# UWB-Breakout.net
KiCad netlist of a schematic drawn in EAGLE
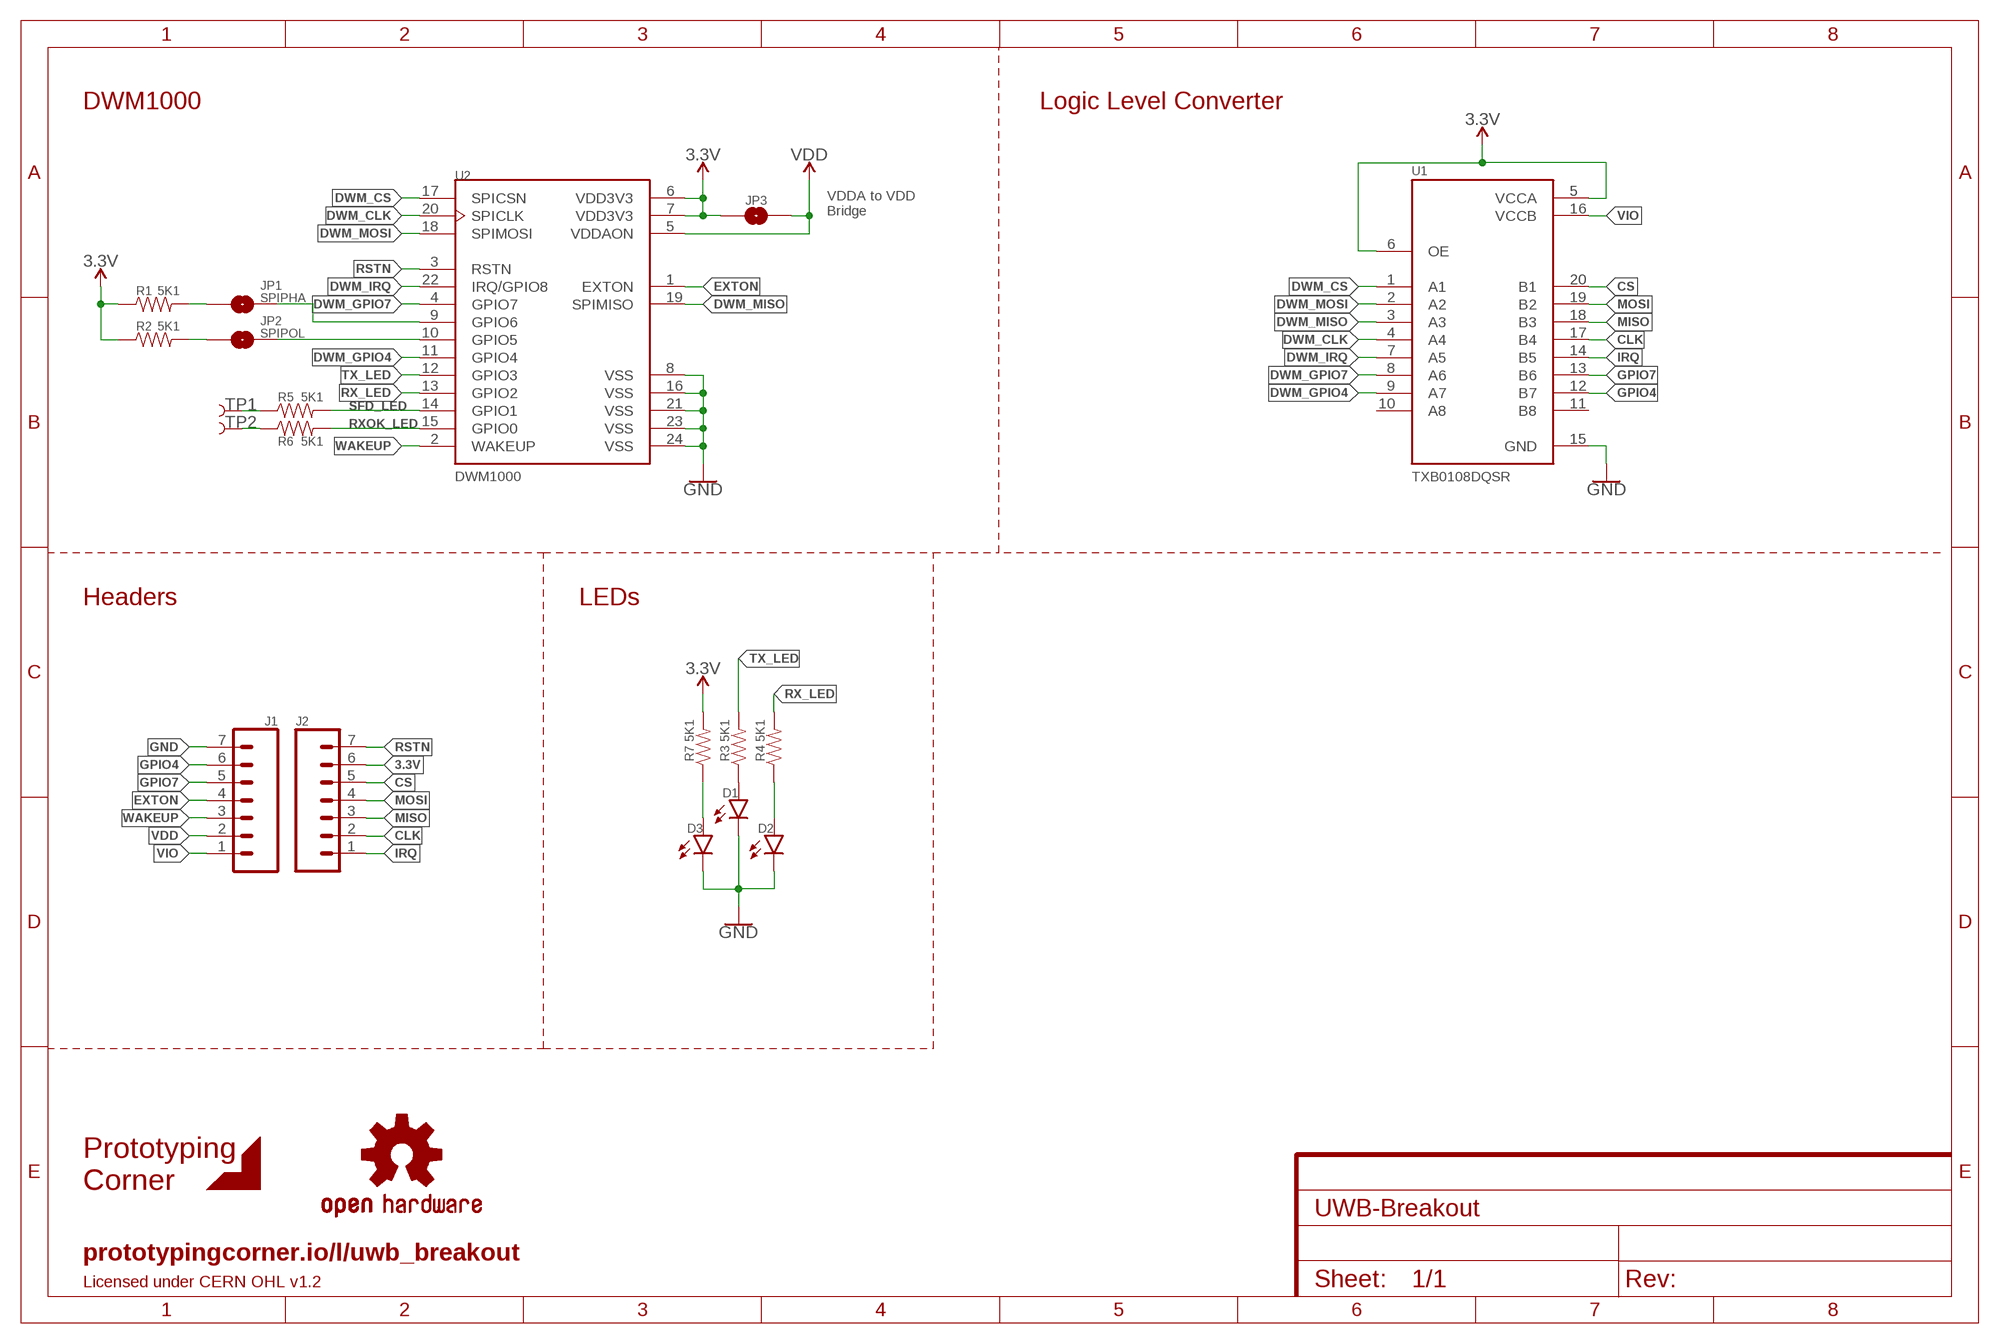
[diagram p0: schematic, sheet 1]

(export (version "E")
  (design (tool "Eeschema 10.0.6"))
  (components
    (comp (ref "D1")
      (value "Yellow")
      (footprint "eagle-import:LED-0603")
      (libsource (lib "eagle-import") (part "LED-YELLOW0603"))
    )
    (comp (ref "D2")
      (value "GREEN")
      (footprint "eagle-import:LED-0603")
      (libsource (lib "eagle-import") (part "LED-GREEN0603"))
    )
    (comp (ref "D3")
      (value "BLUE")
      (footprint "eagle-import:LED-0603")
      (libsource (lib "eagle-import") (part "LED-BLUE0603"))
    )
    (comp (ref "J1")
      (value "CONN_07NO_SILK")
      (footprint "eagle-import:1X07_NO_SILK")
      (libsource (lib "eagle-import") (part "CONN_07NO_SILK"))
    )
    (comp (ref "J2")
      (value "CONN_07NO_SILK")
      (footprint "eagle-import:1X07_NO_SILK")
      (libsource (lib "eagle-import") (part "CONN_07NO_SILK"))
    )
    (comp (ref "JP1")
      (value "SPIPHA")
      (footprint "eagle-import:SMT-JUMPER_2_NO_SILK")
      (libsource (lib "eagle-import") (part "JUMPER-SMT_2_NO_SILK"))
    )
    (comp (ref "JP2")
      (value "SPIPOL")
      (footprint "eagle-import:SMT-JUMPER_2_NO_SILK")
      (libsource (lib "eagle-import") (part "JUMPER-SMT_2_NO_SILK"))
    )
    (comp (ref "JP3")
      (value "JUMPER-SMT_2_NO_SILK")
      (footprint "eagle-import:SMT-JUMPER_2_NO_SILK")
      (libsource (lib "eagle-import") (part "JUMPER-SMT_2_NO_SILK"))
    )
    (comp (ref "LOGO1")
      (value "OSHW-LOGOM")
      (footprint "eagle-import:OSHW-LOGO-M")
      (libsource (lib "eagle-import") (part "OSHW-LOGOM"))
    )
    (comp (ref "R1")
      (value "5K1")
      (footprint "eagle-import:0603")
      (libsource (lib "eagle-import") (part "RESISTOR0603"))
    )
    (comp (ref "R2")
      (value "5K1")
      (footprint "eagle-import:0603")
      (libsource (lib "eagle-import") (part "RESISTOR0603"))
    )
    (comp (ref "R3")
      (value "5K1")
      (footprint "eagle-import:0603")
      (libsource (lib "eagle-import") (part "RESISTOR0603"))
    )
    (comp (ref "R4")
      (value "5K1")
      (footprint "eagle-import:0603")
      (libsource (lib "eagle-import") (part "RESISTOR0603"))
    )
    (comp (ref "R5")
      (value "5K1")
      (footprint "eagle-import:0603")
      (libsource (lib "eagle-import") (part "RESISTOR0603"))
    )
    (comp (ref "R6")
      (value "5K1")
      (footprint "eagle-import:0603")
      (libsource (lib "eagle-import") (part "RESISTOR0603"))
    )
    (comp (ref "R7")
      (value "5K1")
      (footprint "eagle-import:0603")
      (libsource (lib "eagle-import") (part "RESISTOR0603"))
    )
    (comp (ref "TP1")
      (value "TEST-POINT3X5")
      (footprint "eagle-import:PAD.03X.05")
      (libsource (lib "eagle-import") (part "TEST-POINT3X5"))
    )
    (comp (ref "TP2")
      (value "TEST-POINT3X5")
      (footprint "eagle-import:PAD.03X.05")
      (libsource (lib "eagle-import") (part "TEST-POINT3X5"))
    )
    (comp (ref "U1")
      (value "TXB0108DQSR")
      (footprint "eagle-import:SON40P400X200X55-20N")
      (fields (field (name "DIGI-KEY_PART_NUMBER") "296-27217-1-ND") (field (name "MF") "Texas Instruments"))
      (libsource (lib "eagle-import") (part "TXB0108DQSR"))
    )
    (comp (ref "U2")
      (value "DWM1000")
      (footprint "eagle-import:XCVR_DWM1000")
      (fields (field (name "MF") "Decawave Limited"))
      (libsource (lib "eagle-import") (part "DWM1000"))
    )
  )
  (nets
    (net (code "1") (name "/RXOK_LED") (class "Default")
      (node (ref "R6") (pin "2") (pinfunction "2_2") (pintype "passive"))
      (node (ref "U2") (pin "15") (pinfunction "GPIO0_15") (pintype "bidirectional"))
    )
    (net (code "2") (name "/SFD_LED") (class "Default")
      (node (ref "R5") (pin "2") (pinfunction "2_2") (pintype "passive"))
      (node (ref "U2") (pin "14") (pinfunction "GPIO1_14") (pintype "bidirectional"))
    )
    (net (code "3") (name "3.3V") (class "Default")
      (node (ref "J2") (pin "6") (pinfunction "6_6") (pintype "passive"))
      (node (ref "JP3") (pin "1") (pinfunction "1_1") (pintype "passive"))
      (node (ref "R1") (pin "1") (pinfunction "1_1") (pintype "passive"))
      (node (ref "R2") (pin "1") (pinfunction "1_1") (pintype "passive"))
      (node (ref "R7") (pin "2") (pinfunction "2_2") (pintype "passive"))
      (node (ref "U1") (pin "5") (pinfunction "VCCA_5") (pintype "power_in"))
      (node (ref "U1") (pin "6") (pinfunction "OE_6") (pintype "input"))
      (node (ref "U2") (pin "6") (pinfunction "VDD3V3_6") (pintype "power_in"))
      (node (ref "U2") (pin "7") (pinfunction "VDD3V3_7") (pintype "power_in"))
    )
    (net (code "4") (name "CLK") (class "Default")
      (node (ref "J2") (pin "2") (pinfunction "2_2") (pintype "passive"))
      (node (ref "U1") (pin "17") (pinfunction "B4_17") (pintype "bidirectional"))
    )
    (net (code "5") (name "CS") (class "Default")
      (node (ref "J2") (pin "5") (pinfunction "5_5") (pintype "passive"))
      (node (ref "U1") (pin "20") (pinfunction "B1_20") (pintype "bidirectional"))
    )
    (net (code "6") (name "DWM_CLK") (class "Default")
      (node (ref "U1") (pin "4") (pinfunction "A4_4") (pintype "bidirectional"))
      (node (ref "U2") (pin "20") (pinfunction "SPICLK_20") (pintype "input"))
    )
    (net (code "7") (name "DWM_CS") (class "Default")
      (node (ref "U1") (pin "1") (pinfunction "A1_1") (pintype "bidirectional"))
      (node (ref "U2") (pin "17") (pinfunction "SPICSN_17") (pintype "input"))
    )
    (net (code "8") (name "DWM_GPIO4") (class "Default")
      (node (ref "U1") (pin "9") (pinfunction "A7_9") (pintype "bidirectional"))
      (node (ref "U2") (pin "11") (pinfunction "GPIO4_11") (pintype "bidirectional"))
    )
    (net (code "9") (name "DWM_GPIO7") (class "Default")
      (node (ref "U1") (pin "8") (pinfunction "A6_8") (pintype "bidirectional"))
      (node (ref "U2") (pin "4") (pinfunction "GPIO7_4") (pintype "bidirectional"))
    )
    (net (code "10") (name "DWM_IRQ") (class "Default")
      (node (ref "U1") (pin "7") (pinfunction "A5_7") (pintype "bidirectional"))
      (node (ref "U2") (pin "22") (pinfunction "IRQ/GPIO8_22") (pintype "bidirectional"))
    )
    (net (code "11") (name "DWM_MISO") (class "Default")
      (node (ref "U1") (pin "3") (pinfunction "A3_3") (pintype "bidirectional"))
      (node (ref "U2") (pin "19") (pinfunction "SPIMISO_19") (pintype "output"))
    )
    (net (code "12") (name "DWM_MOSI") (class "Default")
      (node (ref "U1") (pin "2") (pinfunction "A2_2") (pintype "bidirectional"))
      (node (ref "U2") (pin "18") (pinfunction "SPIMOSI_18") (pintype "input"))
    )
    (net (code "13") (name "EXTON") (class "Default")
      (node (ref "J1") (pin "4") (pinfunction "4_4") (pintype "passive"))
      (node (ref "U2") (pin "1") (pinfunction "EXTON_1") (pintype "output"))
    )
    (net (code "14") (name "GND") (class "Default")
      (node (ref "D1") (pin "C") (pinfunction "C_C") (pintype "passive"))
      (node (ref "D2") (pin "C") (pinfunction "C_C") (pintype "passive"))
      (node (ref "D3") (pin "C") (pinfunction "C_C") (pintype "passive"))
      (node (ref "J1") (pin "7") (pinfunction "7_7") (pintype "passive"))
      (node (ref "U1") (pin "15") (pinfunction "GND_15") (pintype "power_in"))
      (node (ref "U2") (pin "16") (pinfunction "VSS_16") (pintype "power_in"))
      (node (ref "U2") (pin "21") (pinfunction "VSS_21") (pintype "power_in"))
      (node (ref "U2") (pin "23") (pinfunction "VSS_23") (pintype "power_in"))
      (node (ref "U2") (pin "24") (pinfunction "VSS_24") (pintype "power_in"))
      (node (ref "U2") (pin "8") (pinfunction "VSS_8") (pintype "power_in"))
    )
    (net (code "15") (name "GPIO4") (class "Default")
      (node (ref "J1") (pin "6") (pinfunction "6_6") (pintype "passive"))
      (node (ref "U1") (pin "12") (pinfunction "B7_12") (pintype "bidirectional"))
    )
    (net (code "16") (name "GPIO7") (class "Default")
      (node (ref "J1") (pin "5") (pinfunction "5_5") (pintype "passive"))
      (node (ref "U1") (pin "13") (pinfunction "B6_13") (pintype "bidirectional"))
    )
    (net (code "17") (name "IRQ") (class "Default")
      (node (ref "J2") (pin "1") (pinfunction "1_1") (pintype "passive"))
      (node (ref "U1") (pin "14") (pinfunction "B5_14") (pintype "bidirectional"))
    )
    (net (code "18") (name "MISO") (class "Default")
      (node (ref "J2") (pin "3") (pinfunction "3_3") (pintype "passive"))
      (node (ref "U1") (pin "18") (pinfunction "B3_18") (pintype "bidirectional"))
    )
    (net (code "19") (name "MOSI") (class "Default")
      (node (ref "J2") (pin "4") (pinfunction "4_4") (pintype "passive"))
      (node (ref "U1") (pin "19") (pinfunction "B2_19") (pintype "bidirectional"))
    )
    (net (code "20") (name "Net-(D1-PadA)") (class "Default")
      (node (ref "D1") (pin "A") (pinfunction "A_A") (pintype "passive"))
      (node (ref "R3") (pin "1") (pinfunction "1_1") (pintype "passive"))
    )
    (net (code "21") (name "Net-(D2-PadA)") (class "Default")
      (node (ref "D2") (pin "A") (pinfunction "A_A") (pintype "passive"))
      (node (ref "R4") (pin "1") (pinfunction "1_1") (pintype "passive"))
    )
    (net (code "22") (name "Net-(D3-PadA)") (class "Default")
      (node (ref "D3") (pin "A") (pinfunction "A_A") (pintype "passive"))
      (node (ref "R7") (pin "1") (pinfunction "1_1") (pintype "passive"))
    )
    (net (code "23") (name "Net-(JP1-Pad1)") (class "Default")
      (node (ref "JP1") (pin "1") (pinfunction "1_1") (pintype "passive"))
      (node (ref "R1") (pin "2") (pinfunction "2_2") (pintype "passive"))
    )
    (net (code "24") (name "Net-(JP2-Pad1)") (class "Default")
      (node (ref "JP2") (pin "1") (pinfunction "1_1") (pintype "passive"))
      (node (ref "R2") (pin "2") (pinfunction "2_2") (pintype "passive"))
    )
    (net (code "25") (name "Net-(TP1-1)") (class "Default")
      (node (ref "R5") (pin "1") (pinfunction "1_1") (pintype "passive"))
      (node (ref "TP1") (pin "P$1") (pinfunction "1_P$1") (pintype "bidirectional"))
    )
    (net (code "26") (name "Net-(TP2-1)") (class "Default")
      (node (ref "R6") (pin "1") (pinfunction "1_1") (pintype "passive"))
      (node (ref "TP2") (pin "P$1") (pinfunction "1_P$1") (pintype "bidirectional"))
    )
    (net (code "27") (name "Net-(U2-GPIO5)") (class "Default")
      (node (ref "JP2") (pin "2") (pinfunction "2_2") (pintype "passive"))
      (node (ref "U2") (pin "10") (pinfunction "GPIO5_10") (pintype "bidirectional"))
    )
    (net (code "28") (name "Net-(U2-GPIO6)") (class "Default")
      (node (ref "JP1") (pin "2") (pinfunction "2_2") (pintype "passive"))
      (node (ref "U2") (pin "9") (pinfunction "GPIO6_9") (pintype "bidirectional"))
    )
    (net (code "29") (name "RSTN") (class "Default")
      (node (ref "J2") (pin "7") (pinfunction "7_7") (pintype "passive"))
      (node (ref "U2") (pin "3") (pinfunction "RSTN_3") (pintype "bidirectional"))
    )
    (net (code "30") (name "RX_LED") (class "Default")
      (node (ref "R4") (pin "2") (pinfunction "2_2") (pintype "passive"))
      (node (ref "U2") (pin "13") (pinfunction "GPIO2_13") (pintype "bidirectional"))
    )
    (net (code "31") (name "TX_LED") (class "Default")
      (node (ref "R3") (pin "2") (pinfunction "2_2") (pintype "passive"))
      (node (ref "U2") (pin "12") (pinfunction "GPIO3_12") (pintype "bidirectional"))
    )
    (net (code "32") (name "VDD") (class "Default")
      (node (ref "J1") (pin "2") (pinfunction "2_2") (pintype "passive"))
      (node (ref "JP3") (pin "2") (pinfunction "2_2") (pintype "passive"))
      (node (ref "U2") (pin "5") (pinfunction "VDDAON_5") (pintype "power_in"))
    )
    (net (code "33") (name "VIO") (class "Default")
      (node (ref "J1") (pin "1") (pinfunction "1_1") (pintype "passive"))
      (node (ref "U1") (pin "16") (pinfunction "VCCB_16") (pintype "power_in"))
    )
    (net (code "34") (name "WAKEUP") (class "Default")
      (node (ref "J1") (pin "3") (pinfunction "3_3") (pintype "passive"))
      (node (ref "U2") (pin "2") (pinfunction "WAKEUP_2") (pintype "bidirectional"))
    )
    (net (code "35") (name "unconnected-(U1-A8-Pad10)") (class "Default")
      (node (ref "U1") (pin "10") (pinfunction "A8_10") (pintype "bidirectional"))
    )
    (net (code "36") (name "unconnected-(U1-B8-Pad11)") (class "Default")
      (node (ref "U1") (pin "11") (pinfunction "B8_11") (pintype "bidirectional"))
    )
  )
)
